# LTC4020_Controller.net
KiCad netlist of a schematic drawn in Altium Designer
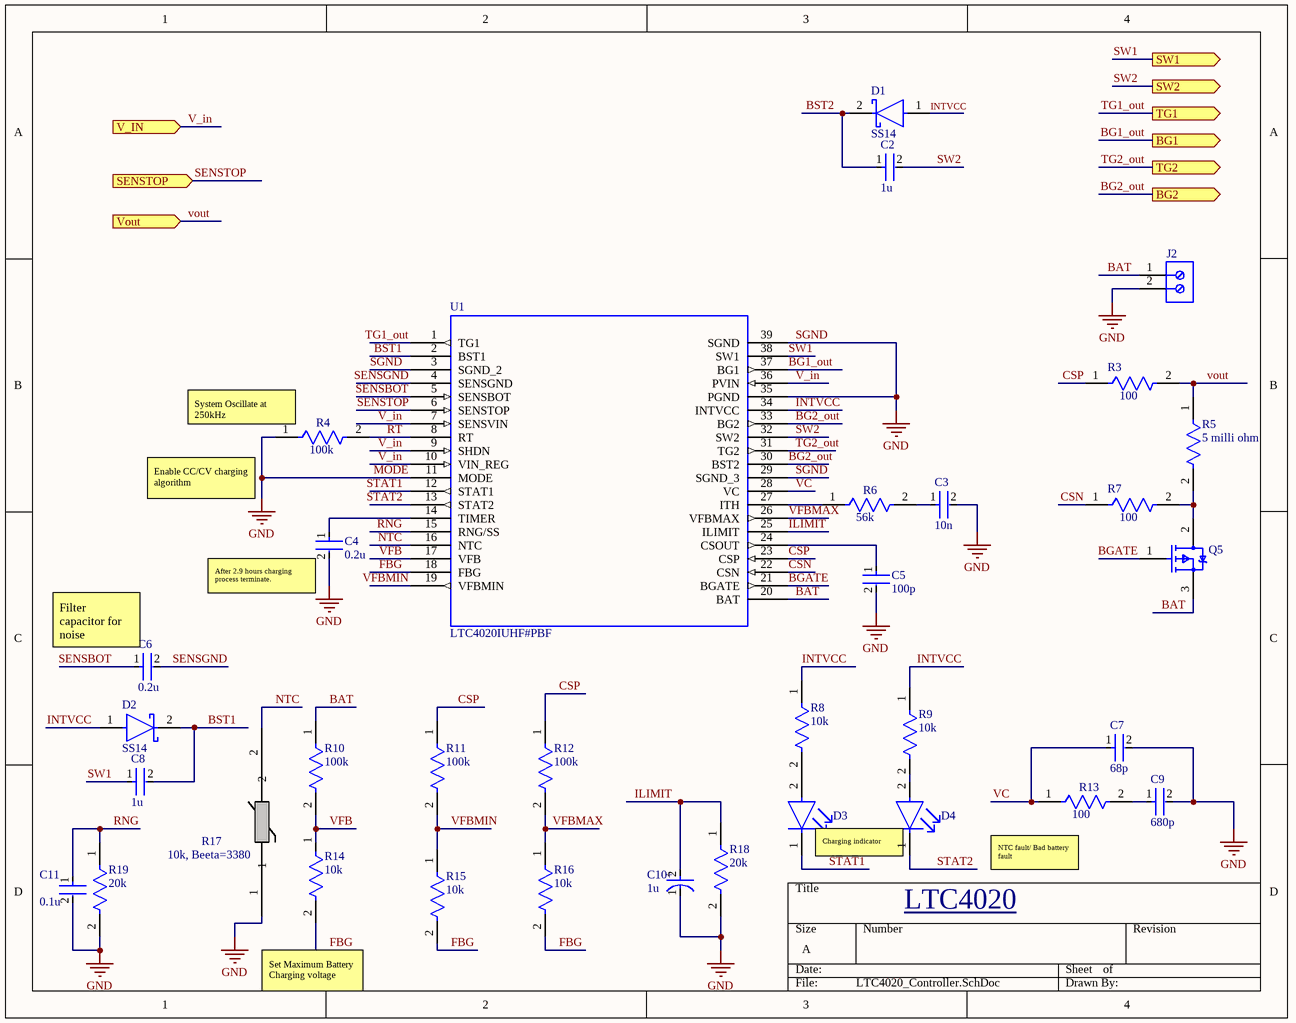
[diagram p0: LTC4020_Controller.SchDoc]

(export (version "E")
  (design (tool "Eeschema 10.0.6"))
  (components
    (comp (ref "C2")
      (value "1u")
      (footprint "FP-C0805C-DN-MFG")
      (description "CAP CER 0.1UF 50V X7R 0805")
      (fields
        (field (name "MANUFACTURER PART NUMBER") "C0805C104K5RACTU")
        (field (name "MANUFACTURER") "KEMET")
      )
      (libsource (lib "Altium Content Vault") (part "b4654b650e69147ec39a6b967a45e02"))
    )
    (comp (ref "C3")
      (value "10n")
      (footprint "FP-C0805C-DN-MFG")
      (description "CAP CER 0.1UF 50V X7R 0805")
      (fields
        (field (name "MANUFACTURER PART NUMBER") "C0805C104K5RACTU")
        (field (name "MANUFACTURER") "KEMET")
      )
      (libsource (lib "Altium Content Vault") (part "b4654b650e69147ec39a6b967a45e02"))
    )
    (comp (ref "C4")
      (value "0.2u")
      (footprint "FP-C0805C-DN-MFG")
      (description "CAP CER 0.1UF 50V X7R 0805")
      (fields
        (field (name "MANUFACTURER PART NUMBER") "C0805C104K5RACTU")
        (field (name "MANUFACTURER") "KEMET")
      )
      (libsource (lib "Altium Content Vault") (part "b4654b650e69147ec39a6b967a45e02"))
    )
    (comp (ref "C5")
      (value "100p")
      (footprint "FP-C0805C-DN-MFG")
      (description "CAP CER 0.1UF 50V X7R 0805")
      (fields
        (field (name "MANUFACTURER PART NUMBER") "C0805C104K5RACTU")
        (field (name "MANUFACTURER") "KEMET")
      )
      (libsource (lib "Altium Content Vault") (part "b4654b650e69147ec39a6b967a45e02"))
    )
    (comp (ref "C6")
      (value "0.2u")
      (footprint "FP-C0805C-DN-MFG")
      (description "CAP CER 0.1UF 50V X7R 0805")
      (fields
        (field (name "MANUFACTURER PART NUMBER") "C0805C104K5RACTU")
        (field (name "MANUFACTURER") "KEMET")
      )
      (libsource (lib "Altium Content Vault") (part "b4654b650e69147ec39a6b967a45e02"))
    )
    (comp (ref "C7")
      (value "68p")
      (footprint "FP-C0805C-DN-MFG")
      (description "CAP CER 0.1UF 50V X7R 0805")
      (fields
        (field (name "MANUFACTURER PART NUMBER") "C0805C104K5RACTU")
        (field (name "MANUFACTURER") "KEMET")
      )
      (libsource (lib "Altium Content Vault") (part "b4654b650e69147ec39a6b967a45e02"))
    )
    (comp (ref "C8")
      (value "1u")
      (footprint "FP-C0805C-DN-MFG")
      (description "CAP CER 0.1UF 50V X7R 0805")
      (fields
        (field (name "MANUFACTURER PART NUMBER") "C0805C104K5RACTU")
        (field (name "MANUFACTURER") "KEMET")
      )
      (libsource (lib "Altium Content Vault") (part "b4654b650e69147ec39a6b967a45e02"))
    )
    (comp (ref "C9")
      (value "680p")
      (footprint "FP-C0805C-DN-MFG")
      (description "CAP CER 0.1UF 50V X7R 0805")
      (fields
        (field (name "MANUFACTURER PART NUMBER") "C0805C104K5RACTU")
        (field (name "MANUFACTURER") "KEMET")
      )
      (libsource (lib "Altium Content Vault") (part "b4654b650e69147ec39a6b967a45e02"))
    )
    (comp (ref "C10")
      (value "1u")
      (footprint "FP-RAD-TH-D_10_0_5-L_16_1-MFG")
      (description "Aluminum Electrolytic Capacitors (Radial Lead Type) AEC-Q200 Qualified 820uF ±20% 10V")
      (fields (field (name "VOLTAGE") "10V") (field (name "TOLERANCE") "20%"))
      (libsource (lib "Altium Content Vault") (part "a00bbbee19879c290e62620ae7e47b1"))
    )
    (comp (ref "C11")
      (value "0.1u")
      (footprint "FP-C0805C-DN-MFG")
      (description "CAP CER 0.1UF 50V X7R 0805")
      (fields
        (field (name "MANUFACTURER PART NUMBER") "C0805C104K5RACTU")
        (field (name "MANUFACTURER") "KEMET")
      )
      (libsource (lib "Altium Content Vault") (part "b4654b650e69147ec39a6b967a45e02"))
    )
    (comp (ref "D1")
      (value "SS14")
      (footprint "FP-403AE-MFG")
      (description "DIODE SCHOTTKY 40V 1A SMA")
      (fields
        (field (name "MANUFACTURER") "ON Semiconductor")
        (field (name "OCTOPART") "https://octopart.com/ss14-on+semiconductor-29205033")
      )
      (libsource (lib "Altium Content Vault") (part "360ad2f4ac25a952324d13796385471"))
    )
    (comp (ref "D2")
      (value "SS14")
      (footprint "FP-403AE-MFG")
      (description "DIODE SCHOTTKY 40V 1A SMA")
      (fields
        (field (name "MANUFACTURER") "ON Semiconductor")
        (field (name "OCTOPART") "https://octopart.com/ss14-on+semiconductor-29205033")
      )
      (libsource (lib "Altium Content Vault") (part "360ad2f4ac25a952324d13796385471"))
    )
    (comp (ref "D3")
      (value "APHCM2012CGCK-F01")
      (footprint "FP-APHCM2012CGCK-F01-MFG")
      (description "LED GREEN CLEAR CHIP SMD")
      (libsource (lib "Altium Content Vault") (part "8706943c75ba83719d021d2fdc84c58"))
    )
    (comp (ref "D4")
      (value "APHCM2012CGCK-F01")
      (footprint "FP-APHCM2012CGCK-F01-MFG")
      (description "LED RED CLEAR CHIP SMD")
      (libsource (lib "Altium Content Vault") (part "8706943c75ba83719d021d2fdc84c58"))
    )
    (comp (ref "J2")
      (value "691134710002")
      (footprint "691134710002")
      (description "Wire-To-Board Terminal Block, 5mm Pitch, Horizontal, Screw, 2 Poles")
      (libsource (lib "Altium Content Vault") (part "TBL - 1R - 02P - Screw"))
    )
    (comp (ref "Q5")
      (value "IRF4905PBF")
      (footprint "FP-PG-TO220-3-MFG")
      (description "MOSFET P-CH 55V 74A TO-220AB")
      (libsource (lib "Altium Content Vault") (part "7c43f5ccbd0f8ca8bbf61673af0f16f"))
    )
    (comp (ref "R3")
      (value "100")
      (footprint "FP-MCU0805-IPC_C")
      (description "RES 1.05K OHM 0.5% 1/5W 0805")
      (libsource (lib "Altium Content Vault") (part "1029c3af85768c4190bb7ad29bc67b5"))
    )
    (comp (ref "R4")
      (value "100k")
      (footprint "FP-MCU0805-IPC_C")
      (description "RES 1.05K OHM 0.5% 1/5W 0805")
      (libsource (lib "Altium Content Vault") (part "1029c3af85768c4190bb7ad29bc67b5"))
    )
    (comp (ref "R5")
      (value "5 milli ohm")
      (footprint "FP-WSLP2512-0R001-0R0049-MFG")
      (libsource (lib "Altium Content Vault") (part "1029c3af85768c4190bb7ad29bc67b5"))
    )
    (comp (ref "R6")
      (value "56k")
      (footprint "FP-MCU0805-IPC_C")
      (description "RES 1.05K OHM 0.5% 1/5W 0805")
      (libsource (lib "Altium Content Vault") (part "1029c3af85768c4190bb7ad29bc67b5"))
    )
    (comp (ref "R7")
      (value "100")
      (footprint "FP-MCU0805-IPC_C")
      (description "RES 1.05K OHM 0.5% 1/5W 0805")
      (libsource (lib "Altium Content Vault") (part "1029c3af85768c4190bb7ad29bc67b5"))
    )
    (comp (ref "R8")
      (value "10k")
      (footprint "FP-MCU0805-IPC_C")
      (description "RES 1.05K OHM 0.5% 1/5W 0805")
      (libsource (lib "Altium Content Vault") (part "1029c3af85768c4190bb7ad29bc67b5"))
    )
    (comp (ref "R9")
      (value "10k")
      (footprint "FP-MCU0805-IPC_C")
      (description "RES 1.05K OHM 0.5% 1/5W 0805")
      (libsource (lib "Altium Content Vault") (part "1029c3af85768c4190bb7ad29bc67b5"))
    )
    (comp (ref "R10")
      (value "100k")
      (footprint "FP-MCU0805-IPC_C")
      (description "RES 1.05K OHM 0.5% 1/5W 0805")
      (libsource (lib "Altium Content Vault") (part "1029c3af85768c4190bb7ad29bc67b5"))
    )
    (comp (ref "R11")
      (value "100k")
      (footprint "FP-MCU0805-IPC_C")
      (description "RES 1.05K OHM 0.5% 1/5W 0805")
      (libsource (lib "Altium Content Vault") (part "1029c3af85768c4190bb7ad29bc67b5"))
    )
    (comp (ref "R12")
      (value "100k")
      (footprint "FP-MCU0805-IPC_C")
      (description "RES 1.05K OHM 0.5% 1/5W 0805")
      (libsource (lib "Altium Content Vault") (part "1029c3af85768c4190bb7ad29bc67b5"))
    )
    (comp (ref "R13")
      (value "100")
      (footprint "FP-MCU0805-IPC_C")
      (description "RES 1.05K OHM 0.5% 1/5W 0805")
      (libsource (lib "Altium Content Vault") (part "1029c3af85768c4190bb7ad29bc67b5"))
    )
    (comp (ref "R14")
      (value "10k")
      (footprint "FP-MCU0805-IPC_C")
      (description "RES 1.05K OHM 0.5% 1/5W 0805")
      (libsource (lib "Altium Content Vault") (part "1029c3af85768c4190bb7ad29bc67b5"))
    )
    (comp (ref "R15")
      (value "10k")
      (footprint "FP-MCU0805-IPC_C")
      (description "RES 1.05K OHM 0.5% 1/5W 0805")
      (libsource (lib "Altium Content Vault") (part "1029c3af85768c4190bb7ad29bc67b5"))
    )
    (comp (ref "R16")
      (value "10k")
      (footprint "FP-MCU0805-IPC_C")
      (description "RES 1.05K OHM 0.5% 1/5W 0805")
      (libsource (lib "Altium Content Vault") (part "1029c3af85768c4190bb7ad29bc67b5"))
    )
    (comp (ref "R17")
      (value "10k, Beeta=3380")
      (footprint "NTCS0805_VIS")
      (fields (field (name "TOLERANCE") "1%"))
      (libsource (lib "Altium Content Vault") (part "NTCS0805E3153FMT"))
    )
    (comp (ref "R18")
      (value "20k")
      (footprint "FP-MCU0805-IPC_C")
      (description "RES 1.05K OHM 0.5% 1/5W 0805")
      (libsource (lib "Altium Content Vault") (part "1029c3af85768c4190bb7ad29bc67b5"))
    )
    (comp (ref "R19")
      (value "20k")
      (footprint "FP-MCU0805-IPC_C")
      (description "RES 1.05K OHM 0.5% 1/5W 0805")
      (libsource (lib "Altium Content Vault") (part "1029c3af85768c4190bb7ad29bc67b5"))
    )
    (comp (ref "U1")
      (value "LTC4020IUHF#PBF")
      (footprint "QFN-38_UHF")
      (description "55V Buck-Boost Multi-Chemistry Battery Charger")
      (fields (field (name "MF") "Analog Devices"))
      (libsource (lib "LTC4020IUHF_PBF") (part "LTC4020IUHF#PBF"))
    )
  )
  (nets
    (net (code "1") (name "/BAT") (class "Default")
      (node (ref "J2") (pin "1") (pinfunction "1_1") (pintype "passive"))
      (node (ref "Q5") (pin "3") (pinfunction "SOURCE_3") (pintype "passive"))
      (node (ref "R10") (pin "1") (pinfunction "1_1") (pintype "passive"))
      (node (ref "U1") (pin "20") (pinfunction "BAT_20") (pintype "passive"))
    )
    (net (code "2") (name "/BG1_out") (class "Default")
      (node (ref "U1") (pin "37") (pinfunction "BG1_37") (pintype "output"))
    )
    (net (code "3") (name "/BG2_out") (class "Default")
      (node (ref "U1") (pin "30") (pinfunction "BST2_30") (pintype "passive"))
      (node (ref "U1") (pin "33") (pinfunction "BG2_33") (pintype "output"))
    )
    (net (code "4") (name "/BGATE") (class "Default")
      (node (ref "Q5") (pin "1") (pinfunction "GATE_1") (pintype "passive"))
      (node (ref "U1") (pin "21") (pinfunction "BGATE_21") (pintype "output"))
    )
    (net (code "5") (name "/BST1") (class "Default")
      (node (ref "C8") (pin "2") (pinfunction "2_2") (pintype "passive"))
      (node (ref "D2") (pin "2") (pinfunction "C_2") (pintype "passive"))
      (node (ref "U1") (pin "2") (pinfunction "BST1_2") (pintype "passive"))
    )
    (net (code "6") (name "/BST2") (class "Default")
      (node (ref "C2") (pin "1") (pinfunction "1_1") (pintype "passive"))
      (node (ref "D1") (pin "2") (pinfunction "C_2") (pintype "passive"))
    )
    (net (code "7") (name "/CSN") (class "Default")
      (node (ref "R7") (pin "1") (pinfunction "1_1") (pintype "passive"))
      (node (ref "U1") (pin "22") (pinfunction "CSN_22") (pintype "input"))
    )
    (net (code "8") (name "/CSP") (class "Default")
      (node (ref "R11") (pin "1") (pinfunction "1_1") (pintype "passive"))
      (node (ref "R12") (pin "1") (pinfunction "1_1") (pintype "passive"))
      (node (ref "R3") (pin "1") (pinfunction "1_1") (pintype "passive"))
      (node (ref "U1") (pin "23") (pinfunction "CSP_23") (pintype "input"))
    )
    (net (code "9") (name "/FBG") (class "Default")
      (node (ref "R14") (pin "2") (pinfunction "2_2") (pintype "passive"))
      (node (ref "R15") (pin "2") (pinfunction "2_2") (pintype "passive"))
      (node (ref "R16") (pin "2") (pinfunction "2_2") (pintype "passive"))
      (node (ref "U1") (pin "18") (pinfunction "FBG_18") (pintype "passive"))
    )
    (net (code "10") (name "/ILIMIT") (class "Default")
      (node (ref "C10") (pin "2") (pinfunction "A_2") (pintype "passive"))
      (node (ref "R18") (pin "1") (pinfunction "1_1") (pintype "passive"))
      (node (ref "U1") (pin "25") (pinfunction "ILIMIT_25") (pintype "passive"))
    )
    (net (code "11") (name "/INTVCC") (class "Default")
      (node (ref "D1") (pin "1") (pinfunction "A_1") (pintype "passive"))
      (node (ref "D2") (pin "1") (pinfunction "A_1") (pintype "passive"))
      (node (ref "R8") (pin "1") (pinfunction "1_1") (pintype "passive"))
      (node (ref "R9") (pin "1") (pinfunction "1_1") (pintype "passive"))
      (node (ref "U1") (pin "34") (pinfunction "INTVCC_34") (pintype "passive"))
    )
    (net (code "12") (name "/NTC") (class "Default")
      (node (ref "R17") (pin "2") (pinfunction "2_2") (pintype "passive"))
      (node (ref "U1") (pin "16") (pinfunction "NTC_16") (pintype "passive"))
    )
    (net (code "13") (name "/RNG") (class "Default")
      (node (ref "C11") (pin "1") (pinfunction "1_1") (pintype "passive"))
      (node (ref "R19") (pin "1") (pinfunction "1_1") (pintype "passive"))
      (node (ref "U1") (pin "15") (pinfunction "RNG/SS_15") (pintype "passive"))
    )
    (net (code "14") (name "/RT") (class "Default")
      (node (ref "R4") (pin "2") (pinfunction "2_2") (pintype "passive"))
      (node (ref "U1") (pin "8") (pinfunction "RT_8") (pintype "passive"))
    )
    (net (code "15") (name "/SENSBOT") (class "Default")
      (node (ref "C6") (pin "1") (pinfunction "1_1") (pintype "passive"))
      (node (ref "U1") (pin "5") (pinfunction "SENSBOT_5") (pintype "input"))
    )
    (net (code "16") (name "/SENSGND") (class "Default")
      (node (ref "C6") (pin "2") (pinfunction "2_2") (pintype "passive"))
      (node (ref "U1") (pin "4") (pinfunction "SENSGND_4") (pintype "passive"))
    )
    (net (code "17") (name "/SENSTOP") (class "Default")
      (node (ref "U1") (pin "6") (pinfunction "SENSTOP_6") (pintype "input"))
    )
    (net (code "18") (name "/STAT1") (class "Default")
      (node (ref "D3") (pin "1") (pinfunction "C_1") (pintype "passive"))
      (node (ref "U1") (pin "12") (pinfunction "STAT1_12") (pintype "output"))
    )
    (net (code "19") (name "/STAT2") (class "Default")
      (node (ref "D4") (pin "1") (pinfunction "C_1") (pintype "passive"))
      (node (ref "U1") (pin "13") (pinfunction "STAT2_13") (pintype "output"))
    )
    (net (code "20") (name "/SW1") (class "Default")
      (node (ref "C8") (pin "1") (pinfunction "1_1") (pintype "passive"))
      (node (ref "U1") (pin "38") (pinfunction "SW1_38") (pintype "passive"))
    )
    (net (code "21") (name "/SW2") (class "Default")
      (node (ref "C2") (pin "2") (pinfunction "2_2") (pintype "passive"))
      (node (ref "U1") (pin "32") (pinfunction "SW2_32") (pintype "passive"))
    )
    (net (code "22") (name "/TG1_out") (class "Default")
      (node (ref "U1") (pin "1") (pinfunction "TG1_1") (pintype "output"))
    )
    (net (code "23") (name "/TG2_out") (class "Default")
      (node (ref "U1") (pin "31") (pinfunction "TG2_31") (pintype "output"))
    )
    (net (code "24") (name "/VC") (class "Default")
      (node (ref "C7") (pin "1") (pinfunction "1_1") (pintype "passive"))
      (node (ref "R13") (pin "1") (pinfunction "1_1") (pintype "passive"))
      (node (ref "U1") (pin "28") (pinfunction "VC_28") (pintype "passive"))
    )
    (net (code "25") (name "/VFB") (class "Default")
      (node (ref "R10") (pin "2") (pinfunction "2_2") (pintype "passive"))
      (node (ref "R14") (pin "1") (pinfunction "1_1") (pintype "passive"))
      (node (ref "U1") (pin "17") (pinfunction "VFB_17") (pintype "passive"))
    )
    (net (code "26") (name "/VFBMAX") (class "Default")
      (node (ref "R12") (pin "2") (pinfunction "2_2") (pintype "passive"))
      (node (ref "R16") (pin "1") (pinfunction "1_1") (pintype "passive"))
      (node (ref "U1") (pin "26") (pinfunction "VFBMAX_26") (pintype "output"))
    )
    (net (code "27") (name "/VFBMIN") (class "Default")
      (node (ref "R11") (pin "2") (pinfunction "2_2") (pintype "passive"))
      (node (ref "R15") (pin "1") (pinfunction "1_1") (pintype "passive"))
      (node (ref "U1") (pin "19") (pinfunction "VFBMIN_19") (pintype "output"))
    )
    (net (code "28") (name "/V_in") (class "Default")
      (node (ref "U1") (pin "10") (pinfunction "VIN_REG_10") (pintype "input"))
      (node (ref "U1") (pin "36") (pinfunction "PVIN_36") (pintype "input"))
      (node (ref "U1") (pin "7") (pinfunction "SENSVIN_7") (pintype "input"))
      (node (ref "U1") (pin "9") (pinfunction "SHDN_9") (pintype "input"))
    )
    (net (code "29") (name "/vout") (class "Default")
      (node (ref "R3") (pin "2") (pinfunction "2_2") (pintype "passive"))
      (node (ref "R5") (pin "1") (pinfunction "1_1") (pintype "passive"))
    )
    (net (code "30") (name "GND") (class "Default")
      (node (ref "C10") (pin "1") (pinfunction "C_1") (pintype "passive"))
      (node (ref "C11") (pin "2") (pinfunction "2_2") (pintype "passive"))
      (node (ref "C3") (pin "2") (pinfunction "2_2") (pintype "passive"))
      (node (ref "C4") (pin "2") (pinfunction "2_2") (pintype "passive"))
      (node (ref "C5") (pin "2") (pinfunction "2_2") (pintype "passive"))
      (node (ref "C7") (pin "2") (pinfunction "2_2") (pintype "passive"))
      (node (ref "C9") (pin "2") (pinfunction "2_2") (pintype "passive"))
      (node (ref "J2") (pin "2") (pinfunction "2_2") (pintype "passive"))
      (node (ref "R17") (pin "1") (pinfunction "1_1") (pintype "passive"))
      (node (ref "R18") (pin "2") (pinfunction "2_2") (pintype "passive"))
      (node (ref "R19") (pin "2") (pinfunction "2_2") (pintype "passive"))
      (node (ref "R4") (pin "1") (pinfunction "1_1") (pintype "passive"))
      (node (ref "U1") (pin "11") (pinfunction "MODE_11") (pintype "passive"))
      (node (ref "U1") (pin "29") (pinfunction "SGND_3_29") (pintype "power_in"))
      (node (ref "U1") (pin "3") (pinfunction "SGND_2_3") (pintype "power_in"))
      (node (ref "U1") (pin "35") (pinfunction "PGND_35") (pintype "power_in"))
      (node (ref "U1") (pin "39") (pinfunction "SGND_39") (pintype "power_in"))
    )
    (net (code "31") (name "Net-(C3-Pad1)") (class "Default")
      (node (ref "C3") (pin "1") (pinfunction "1_1") (pintype "passive"))
      (node (ref "R6") (pin "2") (pinfunction "2_2") (pintype "passive"))
    )
    (net (code "32") (name "Net-(C9-Pad1)") (class "Default")
      (node (ref "C9") (pin "1") (pinfunction "1_1") (pintype "passive"))
      (node (ref "R13") (pin "2") (pinfunction "2_2") (pintype "passive"))
    )
    (net (code "33") (name "Net-(D3-A)") (class "Default")
      (node (ref "D3") (pin "2") (pinfunction "A_2") (pintype "passive"))
      (node (ref "R8") (pin "2") (pinfunction "2_2") (pintype "passive"))
    )
    (net (code "34") (name "Net-(D4-A)") (class "Default")
      (node (ref "D4") (pin "2") (pinfunction "A_2") (pintype "passive"))
      (node (ref "R9") (pin "2") (pinfunction "2_2") (pintype "passive"))
    )
    (net (code "35") (name "Net-(Q5-DRAIN)") (class "Default")
      (node (ref "Q5") (pin "2") (pinfunction "DRAIN_2") (pintype "passive"))
      (node (ref "R5") (pin "2") (pinfunction "2_2") (pintype "passive"))
      (node (ref "R7") (pin "2") (pinfunction "2_2") (pintype "passive"))
    )
    (net (code "36") (name "Net-(U1-CSOUT)") (class "Default")
      (node (ref "C5") (pin "1") (pinfunction "1_1") (pintype "passive"))
      (node (ref "U1") (pin "24") (pinfunction "CSOUT_24") (pintype "output"))
    )
    (net (code "37") (name "Net-(U1-ITH)") (class "Default")
      (node (ref "R6") (pin "1") (pinfunction "1_1") (pintype "passive"))
      (node (ref "U1") (pin "27") (pinfunction "ITH_27") (pintype "passive"))
    )
    (net (code "38") (name "Net-(U1-TIMER)") (class "Default")
      (node (ref "C4") (pin "1") (pinfunction "1_1") (pintype "passive"))
      (node (ref "U1") (pin "14") (pinfunction "TIMER_14") (pintype "passive"))
    )
  )
)
